# external-circuit.net
KiCad netlist of a schematic drawn in Altium Designer
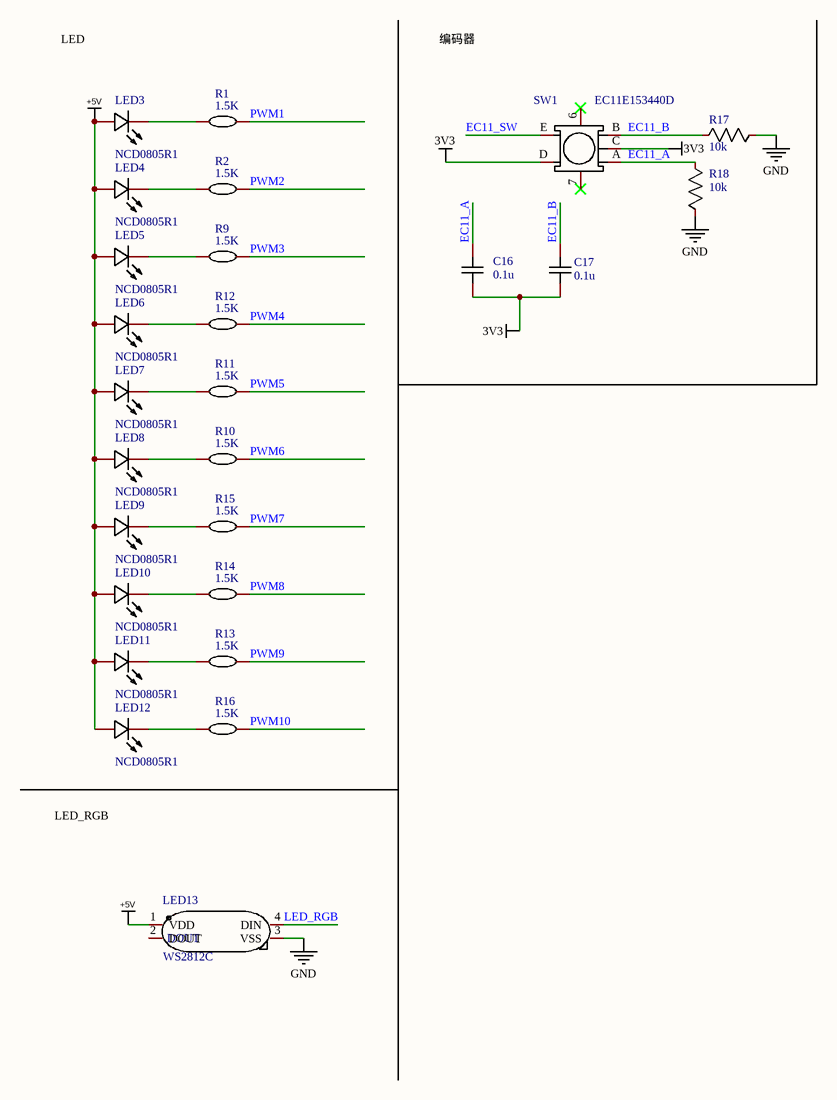
[diagram p0: external-circuit.SchDoc]

(export (version "E")
  (design (tool "Eeschema 10.0.6"))
  (components
    (comp (ref "C16")
      (value "0.1u")
      (footprint "C0805")
      (fields (field (name "NAME") "0.1u"))
      (libsource (lib "altium-import") (part "root_1_0.1u_"))
    )
    (comp (ref "C17")
      (value "0.1u")
      (footprint "C0805")
      (fields (field (name "NAME") "0.1u"))
      (libsource (lib "altium-import") (part "root_1_0.1u_"))
    )
    (comp (ref "LED3")
      (value "NCD0805R1")
      (footprint "LED0805-RD_RED")
      (description "发光颜色:红灯;")
      (fields (field (name "NAME") "NCD0805R1") (field (name "MANUFACTURER") "国星光电"))
      (libsource (lib "altium-import") (part "root_2_NCD0805R1_"))
    )
    (comp (ref "LED4")
      (value "NCD0805R1")
      (footprint "LED0805-RD_RED")
      (description "发光颜色:红灯;")
      (fields (field (name "NAME") "NCD0805R1") (field (name "MANUFACTURER") "国星光电"))
      (libsource (lib "altium-import") (part "root_2_NCD0805R1_"))
    )
    (comp (ref "LED5")
      (value "NCD0805R1")
      (footprint "LED0805-RD_RED")
      (description "发光颜色:红灯;")
      (fields (field (name "NAME") "NCD0805R1") (field (name "MANUFACTURER") "国星光电"))
      (libsource (lib "altium-import") (part "root_2_NCD0805R1_"))
    )
    (comp (ref "LED6")
      (value "NCD0805R1")
      (footprint "LED0805-RD_RED")
      (description "发光颜色:红灯;")
      (fields (field (name "NAME") "NCD0805R1") (field (name "MANUFACTURER") "国星光电"))
      (libsource (lib "altium-import") (part "root_2_NCD0805R1_"))
    )
    (comp (ref "LED7")
      (value "NCD0805R1")
      (footprint "LED0805-RD_RED")
      (description "发光颜色:红灯;")
      (fields (field (name "NAME") "NCD0805R1") (field (name "MANUFACTURER") "国星光电"))
      (libsource (lib "altium-import") (part "root_2_NCD0805R1_"))
    )
    (comp (ref "LED8")
      (value "NCD0805R1")
      (footprint "LED0805-RD_RED")
      (description "发光颜色:红灯;")
      (fields (field (name "NAME") "NCD0805R1") (field (name "MANUFACTURER") "国星光电"))
      (libsource (lib "altium-import") (part "root_2_NCD0805R1_"))
    )
    (comp (ref "LED9")
      (value "NCD0805R1")
      (footprint "LED0805-RD_RED")
      (description "发光颜色:红灯;")
      (fields (field (name "NAME") "NCD0805R1") (field (name "MANUFACTURER") "国星光电"))
      (libsource (lib "altium-import") (part "root_2_NCD0805R1_"))
    )
    (comp (ref "LED10")
      (value "NCD0805R1")
      (footprint "LED0805-RD_RED")
      (description "发光颜色:红灯;")
      (fields (field (name "NAME") "NCD0805R1") (field (name "MANUFACTURER") "国星光电"))
      (libsource (lib "altium-import") (part "root_2_NCD0805R1_"))
    )
    (comp (ref "LED11")
      (value "NCD0805R1")
      (footprint "LED0805-RD_RED")
      (description "发光颜色:红灯;")
      (fields (field (name "NAME") "NCD0805R1") (field (name "MANUFACTURER") "国星光电"))
      (libsource (lib "altium-import") (part "root_2_NCD0805R1_"))
    )
    (comp (ref "LED12")
      (value "NCD0805R1")
      (footprint "LED0805-RD_RED")
      (description "发光颜色:红灯;")
      (fields (field (name "NAME") "NCD0805R1") (field (name "MANUFACTURER") "国星光电"))
      (libsource (lib "altium-import") (part "root_2_NCD0805R1_"))
    )
    (comp (ref "LED13")
      (value "WS2812C")
      (footprint "LED-SMD_4P-L5.0-W5.0-LS5.4-TL-1")
      (description "发光颜色:RGB三色;")
      (fields
        (field (name "NAME") "WS2812C")
        (field (name "MANUFACTURER") "worldsemi")
        (field (name "NAME_1") "DOUT")
      )
      (libsource (lib "altium-import") (part "root_0_WS2812C_"))
    )
    (comp (ref "R1")
      (value "1.5K")
      (footprint "R0805")
      (fields
        (field (name "NAME") "1.5K")
        (field (name "MANUFACTURER") "YAGEO(国巨)")
        (field (name "MANUFACTURER PART") "AC0805FR-071K5L")
      )
      (libsource (lib "altium-import") (part "root_0_AC0805FR-071K5L_"))
    )
    (comp (ref "R2")
      (value "1.5K")
      (footprint "R0805")
      (fields
        (field (name "NAME") "1.5K")
        (field (name "MANUFACTURER") "YAGEO(国巨)")
        (field (name "MANUFACTURER PART") "AC0805FR-071K5L")
      )
      (libsource (lib "altium-import") (part "root_0_AC0805FR-071K5L_"))
    )
    (comp (ref "R9")
      (value "1.5K")
      (footprint "R0805")
      (fields
        (field (name "NAME") "1.5K")
        (field (name "MANUFACTURER") "YAGEO(国巨)")
        (field (name "MANUFACTURER PART") "AC0805FR-071K5L")
      )
      (libsource (lib "altium-import") (part "root_0_AC0805FR-071K5L_"))
    )
    (comp (ref "R10")
      (value "1.5K")
      (footprint "R0805")
      (fields
        (field (name "NAME") "1.5K")
        (field (name "MANUFACTURER") "YAGEO(国巨)")
        (field (name "MANUFACTURER PART") "AC0805FR-071K5L")
      )
      (libsource (lib "altium-import") (part "root_0_AC0805FR-071K5L_"))
    )
    (comp (ref "R11")
      (value "1.5K")
      (footprint "R0805")
      (fields
        (field (name "NAME") "1.5K")
        (field (name "MANUFACTURER") "YAGEO(国巨)")
        (field (name "MANUFACTURER PART") "AC0805FR-071K5L")
      )
      (libsource (lib "altium-import") (part "root_0_AC0805FR-071K5L_"))
    )
    (comp (ref "R12")
      (value "1.5K")
      (footprint "R0805")
      (fields
        (field (name "NAME") "1.5K")
        (field (name "MANUFACTURER") "YAGEO(国巨)")
        (field (name "MANUFACTURER PART") "AC0805FR-071K5L")
      )
      (libsource (lib "altium-import") (part "root_0_AC0805FR-071K5L_"))
    )
    (comp (ref "R13")
      (value "1.5K")
      (footprint "R0805")
      (fields
        (field (name "NAME") "1.5K")
        (field (name "MANUFACTURER") "YAGEO(国巨)")
        (field (name "MANUFACTURER PART") "AC0805FR-071K5L")
      )
      (libsource (lib "altium-import") (part "root_0_AC0805FR-071K5L_"))
    )
    (comp (ref "R14")
      (value "1.5K")
      (footprint "R0805")
      (fields
        (field (name "NAME") "1.5K")
        (field (name "MANUFACTURER") "YAGEO(国巨)")
        (field (name "MANUFACTURER PART") "AC0805FR-071K5L")
      )
      (libsource (lib "altium-import") (part "root_0_AC0805FR-071K5L_"))
    )
    (comp (ref "R15")
      (value "1.5K")
      (footprint "R0805")
      (fields
        (field (name "NAME") "1.5K")
        (field (name "MANUFACTURER") "YAGEO(国巨)")
        (field (name "MANUFACTURER PART") "AC0805FR-071K5L")
      )
      (libsource (lib "altium-import") (part "root_0_AC0805FR-071K5L_"))
    )
    (comp (ref "R16")
      (value "1.5K")
      (footprint "R0805")
      (fields
        (field (name "NAME") "1.5K")
        (field (name "MANUFACTURER") "YAGEO(国巨)")
        (field (name "MANUFACTURER PART") "AC0805FR-071K5L")
      )
      (libsource (lib "altium-import") (part "root_0_AC0805FR-071K5L_"))
    )
    (comp (ref "R17")
      (value "10k")
      (footprint "R0805")
      (fields (field (name "NAME") "10k"))
      (libsource (lib "altium-import") (part "root_2_10k_"))
    )
    (comp (ref "R18")
      (value "10k")
      (footprint "R0805")
      (fields (field (name "NAME") "10k"))
      (libsource (lib "altium-import") (part "root_3_10k_"))
    )
    (comp (ref "SW1")
      (value "EC11E153440D")
      (footprint "SW-TH_EC11XXXXXXXX")
      (fields (field (name "NAME") "EC11E153440D") (field (name "MANUFACTURER") "ALPSALPINE(阿尔卑斯阿尔派)"))
      (libsource (lib "altium-import") (part "root_1_EC11E153440D_"))
    )
  )
  (nets
    (net (code "1") (name "+5V") (class "Default")
      (node (ref "LED10") (pin "2") (pinfunction "+_2") (pintype "passive"))
      (node (ref "LED11") (pin "2") (pinfunction "+_2") (pintype "passive"))
      (node (ref "LED12") (pin "2") (pinfunction "+_2") (pintype "passive"))
      (node (ref "LED13") (pin "1") (pinfunction "VDD_1") (pintype "passive"))
      (node (ref "LED3") (pin "2") (pinfunction "+_2") (pintype "passive"))
      (node (ref "LED4") (pin "2") (pinfunction "+_2") (pintype "passive"))
      (node (ref "LED5") (pin "2") (pinfunction "+_2") (pintype "passive"))
      (node (ref "LED6") (pin "2") (pinfunction "+_2") (pintype "passive"))
      (node (ref "LED7") (pin "2") (pinfunction "+_2") (pintype "passive"))
      (node (ref "LED8") (pin "2") (pinfunction "+_2") (pintype "passive"))
      (node (ref "LED9") (pin "2") (pinfunction "+_2") (pintype "passive"))
    )
    (net (code "2") (name "/EC11_A") (class "Default")
      (node (ref "C16") (pin "2") (pinfunction "2_2") (pintype "passive"))
      (node (ref "R18") (pin "1") (pinfunction "1_1") (pintype "passive"))
      (node (ref "SW1") (pin "A") (pinfunction "A_A") (pintype "passive"))
    )
    (net (code "3") (name "/EC11_B") (class "Default")
      (node (ref "C17") (pin "2") (pinfunction "2_2") (pintype "passive"))
      (node (ref "R17") (pin "2") (pinfunction "2_2") (pintype "passive"))
      (node (ref "SW1") (pin "B") (pinfunction "B_B") (pintype "passive"))
    )
    (net (code "4") (name "/EC11_SW") (class "Default")
      (node (ref "SW1") (pin "E") (pinfunction "E_E") (pintype "passive"))
    )
    (net (code "5") (name "/LED_RGB") (class "Default")
      (node (ref "LED13") (pin "4") (pinfunction "DIN_4") (pintype "passive"))
    )
    (net (code "6") (name "/PWM1") (class "Default")
      (node (ref "R1") (pin "2") (pinfunction "2_2") (pintype "passive"))
    )
    (net (code "7") (name "/PWM2") (class "Default")
      (node (ref "R2") (pin "2") (pinfunction "2_2") (pintype "passive"))
    )
    (net (code "8") (name "/PWM3") (class "Default")
      (node (ref "R9") (pin "2") (pinfunction "2_2") (pintype "passive"))
    )
    (net (code "9") (name "/PWM4") (class "Default")
      (node (ref "R12") (pin "2") (pinfunction "2_2") (pintype "passive"))
    )
    (net (code "10") (name "/PWM5") (class "Default")
      (node (ref "R11") (pin "2") (pinfunction "2_2") (pintype "passive"))
    )
    (net (code "11") (name "/PWM6") (class "Default")
      (node (ref "R10") (pin "2") (pinfunction "2_2") (pintype "passive"))
    )
    (net (code "12") (name "/PWM7") (class "Default")
      (node (ref "R15") (pin "2") (pinfunction "2_2") (pintype "passive"))
    )
    (net (code "13") (name "/PWM8") (class "Default")
      (node (ref "R14") (pin "2") (pinfunction "2_2") (pintype "passive"))
    )
    (net (code "14") (name "/PWM9") (class "Default")
      (node (ref "R13") (pin "2") (pinfunction "2_2") (pintype "passive"))
    )
    (net (code "15") (name "/PWM10") (class "Default")
      (node (ref "R16") (pin "2") (pinfunction "2_2") (pintype "passive"))
    )
    (net (code "16") (name "3V3") (class "Default")
      (node (ref "C16") (pin "1") (pinfunction "1_1") (pintype "passive"))
      (node (ref "C17") (pin "1") (pinfunction "1_1") (pintype "passive"))
      (node (ref "SW1") (pin "C") (pinfunction "C_C") (pintype "passive"))
      (node (ref "SW1") (pin "D") (pinfunction "D_D") (pintype "passive"))
    )
    (net (code "17") (name "GND") (class "Default")
      (node (ref "LED13") (pin "3") (pinfunction "VSS_3") (pintype "passive"))
      (node (ref "R17") (pin "1") (pinfunction "1_1") (pintype "passive"))
      (node (ref "R18") (pin "2") (pinfunction "2_2") (pintype "passive"))
    )
    (net (code "18") (name "Net-(LED3--)") (class "Default")
      (node (ref "LED3") (pin "1") (pinfunction "-_1") (pintype "passive"))
      (node (ref "R1") (pin "1") (pinfunction "1_1") (pintype "passive"))
    )
    (net (code "19") (name "Net-(LED4--)") (class "Default")
      (node (ref "LED4") (pin "1") (pinfunction "-_1") (pintype "passive"))
      (node (ref "R2") (pin "1") (pinfunction "1_1") (pintype "passive"))
    )
    (net (code "20") (name "Net-(LED5--)") (class "Default")
      (node (ref "LED5") (pin "1") (pinfunction "-_1") (pintype "passive"))
      (node (ref "R9") (pin "1") (pinfunction "1_1") (pintype "passive"))
    )
    (net (code "21") (name "Net-(LED6--)") (class "Default")
      (node (ref "LED6") (pin "1") (pinfunction "-_1") (pintype "passive"))
      (node (ref "R12") (pin "1") (pinfunction "1_1") (pintype "passive"))
    )
    (net (code "22") (name "Net-(LED7--)") (class "Default")
      (node (ref "LED7") (pin "1") (pinfunction "-_1") (pintype "passive"))
      (node (ref "R11") (pin "1") (pinfunction "1_1") (pintype "passive"))
    )
    (net (code "23") (name "Net-(LED8--)") (class "Default")
      (node (ref "LED8") (pin "1") (pinfunction "-_1") (pintype "passive"))
      (node (ref "R10") (pin "1") (pinfunction "1_1") (pintype "passive"))
    )
    (net (code "24") (name "Net-(LED9--)") (class "Default")
      (node (ref "LED9") (pin "1") (pinfunction "-_1") (pintype "passive"))
      (node (ref "R15") (pin "1") (pinfunction "1_1") (pintype "passive"))
    )
    (net (code "25") (name "Net-(LED10--)") (class "Default")
      (node (ref "LED10") (pin "1") (pinfunction "-_1") (pintype "passive"))
      (node (ref "R14") (pin "1") (pinfunction "1_1") (pintype "passive"))
    )
    (net (code "26") (name "Net-(LED11--)") (class "Default")
      (node (ref "LED11") (pin "1") (pinfunction "-_1") (pintype "passive"))
      (node (ref "R13") (pin "1") (pinfunction "1_1") (pintype "passive"))
    )
    (net (code "27") (name "Net-(LED12--)") (class "Default")
      (node (ref "LED12") (pin "1") (pinfunction "-_1") (pintype "passive"))
      (node (ref "R16") (pin "1") (pinfunction "1_1") (pintype "passive"))
    )
    (net (code "28") (name "unconnected-(LED13-DOUT-Pad2)") (class "Default")
      (node (ref "LED13") (pin "2") (pinfunction "DOUT_2") (pintype "passive"))
    )
    (net (code "29") (name "unconnected-(SW1-Pad6)") (class "Default")
      (node (ref "SW1") (pin "6") (pinfunction "6_6") (pintype "passive+no_connect"))
    )
    (net (code "30") (name "unconnected-(SW1-Pad7)") (class "Default")
      (node (ref "SW1") (pin "7") (pinfunction "7_7") (pintype "passive+no_connect"))
    )
  )
)
